# ledstringpowerMar2021.net
KiCad netlist of a schematic drawn in EAGLE
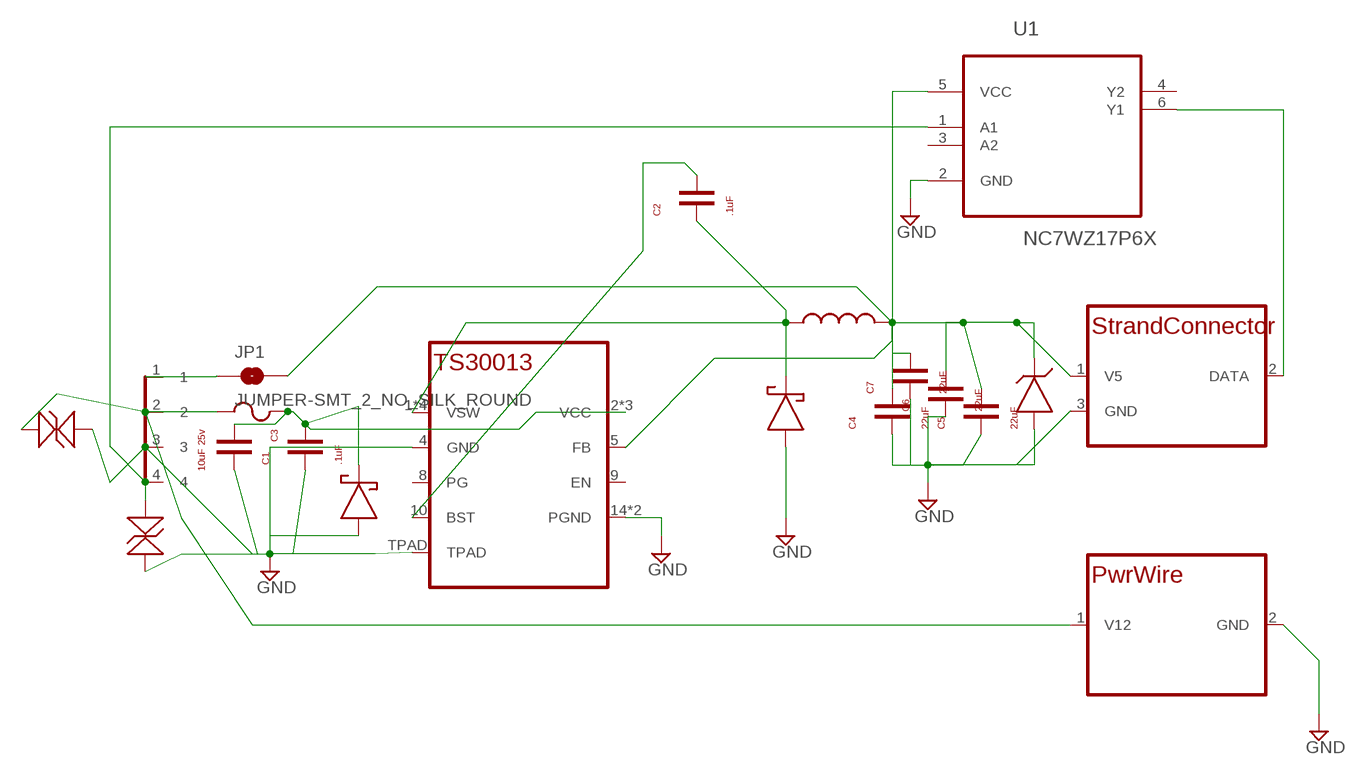
[diagram p0: schematic, sheet 1]

(export (version "E")
  (design (tool "Eeschema 10.0.6"))
  (components
    (comp (ref "C1")
      (value ".1uF")
      (footprint "eagle-import:C0603")
      (libsource (lib "eagle-import") (part "CAPACITOR_NONPOLARC0603"))
    )
    (comp (ref "C2")
      (value ".1uF")
      (footprint "eagle-import:C0603")
      (libsource (lib "eagle-import") (part "CAPACITOR_NONPOLARC0603"))
    )
    (comp (ref "C3")
      (value "10uF 25v")
      (footprint "eagle-import:C1206")
      (libsource (lib "eagle-import") (part "CL31A106MAHNNNEC1206"))
    )
    (comp (ref "C4")
      (value "22uF")
      (footprint "eagle-import:C0603")
      (libsource (lib "eagle-import") (part "GRM188R61A226ME15DC0603"))
    )
    (comp (ref "C5")
      (value "22uF")
      (footprint "eagle-import:C0603")
      (libsource (lib "eagle-import") (part "GRM188R61A226ME15DC0603"))
    )
    (comp (ref "C6")
      (value "22uF")
      (footprint "eagle-import:C0603")
      (libsource (lib "eagle-import") (part "GRM188R61A226ME15DC0603"))
    )
    (comp (ref "C7")
      (value "22uF")
      (footprint "eagle-import:C0603")
      (libsource (lib "eagle-import") (part "GRM188R61A226ME15DC0603"))
    )
    (comp (ref "D2")
      (value "LS54LS54DEVINST")
      (footprint "eagle-import:LS54")
      (libsource (lib "eagle-import") (part "LS54LS54DEVINST"))
    )
    (comp (ref "F1")
      (value "3A")
      (footprint "eagle-import:R0603")
      (libsource (lib "eagle-import") (part "FUSER0603"))
    )
    (comp (ref "IC1")
      (value "TS30013QFN16")
      (footprint "eagle-import:QFN16")
      (libsource (lib "eagle-import") (part "TS30013QFN16"))
    )
    (comp (ref "JP1")
      (value "JUMPER-SMT_2_NO_SILK_ROUND")
      (footprint "eagle-import:SMT-JUMPER_2_NO_SILK_ROUND")
      (libsource (lib "eagle-import") (part "JUMPER-SMT_2_NO_SILK_ROUND"))
    )
    (comp (ref "L1")
      (value "SRN5040TA-4R7MSRN5040TA")
      (footprint "eagle-import:SRN5040TA")
      (libsource (lib "eagle-import") (part "SRN5040TA-4R7MSRN5040TA"))
    )
    (comp (ref "TVS1")
      (value "DESD5V0U1BL-7BDFN1006-2")
      (footprint "eagle-import:DFN1006-2")
      (libsource (lib "eagle-import") (part "DESD5V0U1BL-7BDFN1006-2"))
    )
    (comp (ref "TVS2")
      (value "DESD5V0U1BL-7BDFN1006-2")
      (footprint "eagle-import:DFN1006-2")
      (libsource (lib "eagle-import") (part "DESD5V0U1BL-7BDFN1006-2"))
    )
    (comp (ref "U$1")
      (value "1SMB5930BT3G1SMB5930BT3GDEVINST")
      (footprint "eagle-import:1SMB5930BT3G")
      (libsource (lib "eagle-import") (part "1SMB5930BT3G1SMB5930BT3GDEVINST"))
    )
    (comp (ref "U$2")
      (value "MMSZ5231BT3G-5V1-ZENERSOD123DEVINST")
      (footprint "eagle-import:SOD123")
      (libsource (lib "eagle-import") (part "MMSZ5231BT3G-5V1-ZENERSOD123DEVINST"))
    )
    (comp (ref "U$3")
      (value "TE-1969806-1TE-1969806-1")
      (footprint "eagle-import:TE-1969806-1")
      (libsource (lib "eagle-import") (part "TE-1969806-1TE-1969806-1"))
    )
    (comp (ref "U$5")
      (value "LEDSTRANDDLEDWIREP")
      (footprint "eagle-import:LEDWIREP")
      (libsource (lib "eagle-import") (part "LEDSTRANDDLEDWIREP"))
    )
    (comp (ref "U$8")
      (value "PWRWIREDPWRWIREP")
      (footprint "eagle-import:PWRWIREP")
      (libsource (lib "eagle-import") (part "PWRWIREDPWRWIREP"))
    )
    (comp (ref "U1")
      (value "NC7WZ17P6X")
      (footprint "eagle-import:SOT65P210X110-6N")
      (libsource (lib "eagle-import") (part "NC7WZ17P6X"))
    )
  )
  (nets
    (net (code "1") (name "GND") (class "Default")
      (node (ref "C1") (pin "1") (pinfunction "1_1") (pintype "bidirectional"))
      (node (ref "C3") (pin "2") (pinfunction "2_2") (pintype "bidirectional"))
      (node (ref "C4") (pin "1") (pinfunction "1_1") (pintype "bidirectional"))
      (node (ref "C5") (pin "1") (pinfunction "1_1") (pintype "bidirectional"))
      (node (ref "C6") (pin "1") (pinfunction "1_1") (pintype "bidirectional"))
      (node (ref "C7") (pin "1") (pinfunction "1_1") (pintype "bidirectional"))
      (node (ref "D2") (pin "1") (pinfunction "1_1") (pintype "bidirectional"))
      (node (ref "IC1") (pin "14") (pinfunction "PGND_14") (pintype "bidirectional"))
      (node (ref "IC1") (pin "15") (pinfunction "PGND_15") (pintype "bidirectional"))
      (node (ref "IC1") (pin "4") (pinfunction "GND_4") (pintype "bidirectional"))
      (node (ref "IC1") (pin "TPAD") (pinfunction "TPAD_TPAD") (pintype "bidirectional"))
      (node (ref "TVS1") (pin "1") (pinfunction "1_1") (pintype "bidirectional"))
      (node (ref "TVS2") (pin "1") (pinfunction "1_1") (pintype "bidirectional"))
      (node (ref "U$1") (pin "1") (pinfunction "1_1") (pintype "bidirectional"))
      (node (ref "U$2") (pin "1") (pinfunction "1_1") (pintype "bidirectional"))
      (node (ref "U$3") (pin "3") (pinfunction "3_3") (pintype "bidirectional"))
      (node (ref "U$5") (pin "3") (pinfunction "GND_3") (pintype "bidirectional"))
      (node (ref "U$8") (pin "2") (pinfunction "GND_2") (pintype "bidirectional"))
      (node (ref "U1") (pin "2") (pinfunction "GND_2") (pintype "passive"))
    )
    (net (code "2") (name "Net-(C1-Pad2)") (class "Default")
      (node (ref "C1") (pin "2") (pinfunction "2_2") (pintype "bidirectional"))
      (node (ref "C3") (pin "1") (pinfunction "1_1") (pintype "bidirectional"))
      (node (ref "F1") (pin "2") (pinfunction "2_2") (pintype "bidirectional"))
      (node (ref "IC1") (pin "11") (pinfunction "VCC_11") (pintype "bidirectional"))
      (node (ref "IC1") (pin "2") (pinfunction "VCC_2") (pintype "bidirectional"))
      (node (ref "IC1") (pin "3") (pinfunction "VCC_3") (pintype "bidirectional"))
      (node (ref "U$1") (pin "2") (pinfunction "2_2") (pintype "bidirectional"))
    )
    (net (code "3") (name "Net-(C2-Pad1)") (class "Default")
      (node (ref "C2") (pin "1") (pinfunction "1_1") (pintype "bidirectional"))
      (node (ref "D2") (pin "2") (pinfunction "2_2") (pintype "bidirectional"))
      (node (ref "IC1") (pin "1") (pinfunction "VSW_1") (pintype "bidirectional"))
      (node (ref "IC1") (pin "12") (pinfunction "VSW_12") (pintype "bidirectional"))
      (node (ref "IC1") (pin "13") (pinfunction "VSW_13") (pintype "bidirectional"))
      (node (ref "IC1") (pin "16") (pinfunction "VSW_16") (pintype "bidirectional"))
      (node (ref "L1") (pin "1") (pinfunction "1_1") (pintype "bidirectional"))
    )
    (net (code "4") (name "Net-(IC1-BST)") (class "Default")
      (node (ref "C2") (pin "2") (pinfunction "2_2") (pintype "bidirectional"))
      (node (ref "IC1") (pin "10") (pinfunction "BST_10") (pintype "bidirectional"))
    )
    (net (code "5") (name "Net-(IC1-FB)") (class "Default")
      (node (ref "C4") (pin "2") (pinfunction "2_2") (pintype "bidirectional"))
      (node (ref "C5") (pin "2") (pinfunction "2_2") (pintype "bidirectional"))
      (node (ref "C6") (pin "2") (pinfunction "2_2") (pintype "bidirectional"))
      (node (ref "C7") (pin "2") (pinfunction "2_2") (pintype "bidirectional"))
      (node (ref "IC1") (pin "5") (pinfunction "FB_5") (pintype "bidirectional"))
      (node (ref "JP1") (pin "2") (pinfunction "2_2") (pintype "passive"))
      (node (ref "L1") (pin "2") (pinfunction "2_2") (pintype "bidirectional"))
      (node (ref "U$2") (pin "2") (pinfunction "2_2") (pintype "bidirectional"))
      (node (ref "U$5") (pin "1") (pinfunction "V5_1") (pintype "bidirectional"))
      (node (ref "U1") (pin "5") (pinfunction "VCC_5") (pintype "power_in"))
    )
    (net (code "6") (name "Net-(JP1-Pad1)") (class "Default")
      (node (ref "JP1") (pin "1") (pinfunction "1_1") (pintype "passive"))
      (node (ref "U$3") (pin "1") (pinfunction "1_1") (pintype "bidirectional"))
    )
    (net (code "7") (name "Net-(U$5-DATA)") (class "Default")
      (node (ref "U$5") (pin "2") (pinfunction "DATA_2") (pintype "bidirectional"))
      (node (ref "U1") (pin "6") (pinfunction "Y1_6") (pintype "output"))
    )
    (net (code "8") (name "Net-(U$8-V12)") (class "Default")
      (node (ref "F1") (pin "1") (pinfunction "1_1") (pintype "bidirectional"))
      (node (ref "TVS1") (pin "2") (pinfunction "2_2") (pintype "bidirectional"))
      (node (ref "U$3") (pin "2") (pinfunction "2_2") (pintype "bidirectional"))
      (node (ref "U$8") (pin "1") (pinfunction "V12_1") (pintype "bidirectional"))
    )
    (net (code "9") (name "Net-(U1-A1)") (class "Default")
      (node (ref "TVS2") (pin "2") (pinfunction "2_2") (pintype "bidirectional"))
      (node (ref "U$3") (pin "4") (pinfunction "4_4") (pintype "bidirectional"))
      (node (ref "U1") (pin "1") (pinfunction "A1_1") (pintype "input"))
    )
    (net (code "10") (name "unconnected-(IC1-EN-Pad9)") (class "Default")
      (node (ref "IC1") (pin "9") (pinfunction "EN_9") (pintype "bidirectional"))
    )
    (net (code "11") (name "unconnected-(IC1-PG-Pad8)") (class "Default")
      (node (ref "IC1") (pin "8") (pinfunction "PG_8") (pintype "bidirectional"))
    )
    (net (code "12") (name "unconnected-(U1-A2-Pad3)") (class "Default")
      (node (ref "U1") (pin "3") (pinfunction "A2_3") (pintype "input"))
    )
    (net (code "13") (name "unconnected-(U1-Y2-Pad4)") (class "Default")
      (node (ref "U1") (pin "4") (pinfunction "Y2_4") (pintype "output"))
    )
  )
)
